# LED_Validation_Board_pg_1.net
KiCad netlist of a schematic drawn in Altium Designer
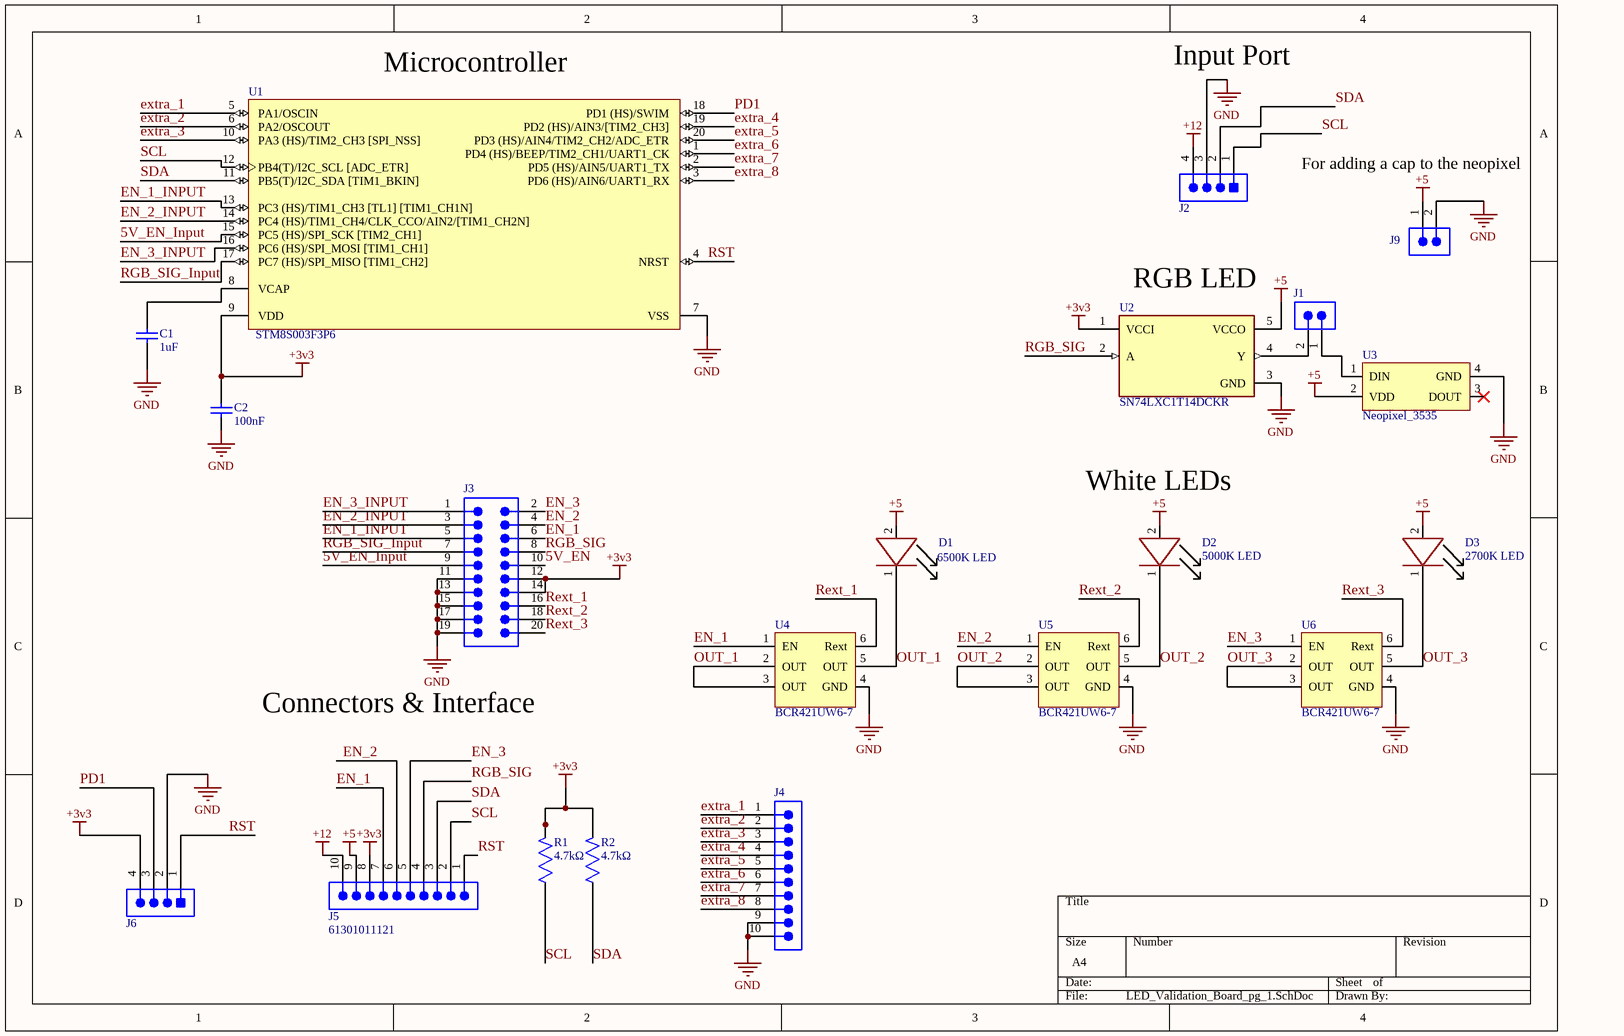
[diagram p0: LED_Validation_Board_pg_1.SchDoc]

(export (version "E")
  (design (tool "Eeschema 10.0.6"))
  (components
    (comp (ref "C1")
      (value "1uF")
      (footprint "0402 PACKAGE")
      (description "CAP CER 1UF 10V X5R 0402")
      (libsource (lib "LED_Validation_Sch_Lib") (part "Capacitor"))
    )
    (comp (ref "C2")
      (value "100nF")
      (footprint "0402 PACKAGE")
      (description "CAP CER 0.1UF 10V X5R 0402")
      (libsource (lib "LED_Validation_Sch_Lib") (part "Capacitor"))
    )
    (comp (ref "D1")
      (value "6500K LED")
      (footprint "2424 Package")
      (description "6500k LED")
      (libsource (lib "LED_Module_Schematic_Library") (part "6500K LED"))
    )
    (comp (ref "D2")
      (value "5000K LED")
      (footprint "2424 Package")
      (description "5000k LED")
      (libsource (lib "LED_Module_Schematic_Library") (part "5000K LED"))
    )
    (comp (ref "D3")
      (value "2700K LED")
      (footprint "2424 Package")
      (description "2700k LED")
      (libsource (lib "LED_Module_Schematic_Library") (part "2700K LED"))
    )
    (comp (ref "J1")
      (value "TSW-102-26-F-S")
      (footprint "SMTC-TSW-102-26-XX-S")
      (description "0.025\" SQ Post Header, Through-hole, Vertical, -55 to 125 degC, 2.54 mm Pitch, 2-Pin, Male, RoHS")
      (fields (field (name "MANUFACTURER") "Samtec"))
      (libsource (lib "Altium Content Vault") (part "SMTC-TSW-102-X-X-S-X"))
    )
    (comp (ref "J2")
      (value "640445-4")
      (footprint "TECO-640445-4_V")
      (fields (field (name "MANUFACTURER") "TE Connectivity"))
      (libsource (lib "Altium Content Vault") (part "CN-1P-M-R4"))
    )
    (comp (ref "J3")
      (value "61302021121")
      (footprint "61302021121")
      (libsource (lib "Altium Content Vault") (part "Header_Male_2R_20P"))
    )
    (comp (ref "J4")
      (value "61301011121")
      (footprint "61301011121")
      (libsource (lib "Altium Content Vault") (part "Header_Male_1R_10P"))
    )
    (comp (ref "J5")
      (value "61301011121")
      (footprint "61301011121")
      (libsource (lib "Altium Content Vault") (part "Header_Male_1R_10P"))
    )
    (comp (ref "J6")
      (value "640445-4")
      (footprint "TECO-640445-4_V")
      (fields (field (name "MANUFACTURER") "TE Connectivity"))
      (libsource (lib "Altium Content Vault") (part "CN-1P-M-R4"))
    )
    (comp (ref "J9")
      (value "TSW-102-26-F-S")
      (footprint "SMTC-TSW-102-26-XX-S")
      (description "0.025\" SQ Post Header, Through-hole, Vertical, -55 to 125 degC, 2.54 mm Pitch, 2-Pin, Male, RoHS")
      (fields (field (name "MANUFACTURER") "Samtec"))
      (libsource (lib "Altium Content Vault") (part "SMTC-TSW-102-X-X-S-X"))
    )
    (comp (ref "R1")
      (value "4.7kΩ")
      (footprint "0402 PACKAGE")
      (libsource (lib "LED_Validation_Sch_Lib") (part "Resistor"))
    )
    (comp (ref "R2")
      (value "4.7kΩ")
      (footprint "0402 PACKAGE")
      (libsource (lib "LED_Validation_Sch_Lib") (part "Resistor"))
    )
    (comp (ref "U1")
      (value "STM8S003F3P6")
      (footprint "STM-TSSOP20_V")
      (fields (field (name "MANUFACTURER") "STMicroelectronics"))
      (libsource (lib "Altium Content Vault") (part "STM-STM8S003F3P6-TSSOP20"))
    )
    (comp (ref "U2")
      (value "SN74LXC1T14DCKR")
      (footprint "FP-DCK0005A-MFG")
      (description "IC TRANSLATOR UNIDIR SC70-5")
      (libsource (lib "Altium Content Vault") (part "307c293e8a03021d4f984951ede828e"))
    )
    (comp (ref "U3")
      (value "Neopixel_3535")
      (footprint "Neopixel")
      (libsource (lib "LED_Validation_Sch_Lib") (part "Neopixel_3535"))
    )
    (comp (ref "U4")
      (value "BCR421UW6-7")
      (footprint "SOT95P280X140-6N")
      (description "LED Driver")
      (libsource (lib "LED_Validation_Sch_Lib") (part "BCR421UW6-7"))
    )
    (comp (ref "U5")
      (value "BCR421UW6-7")
      (footprint "SOT95P280X140-6N")
      (description "LED Driver")
      (libsource (lib "LED_Validation_Sch_Lib") (part "BCR421UW6-7"))
    )
    (comp (ref "U6")
      (value "BCR421UW6-7")
      (footprint "SOT95P280X140-6N")
      (description "LED Driver")
      (libsource (lib "LED_Validation_Sch_Lib") (part "BCR421UW6-7"))
    )
  )
  (nets
    (net (code "1") (name "+3v3") (class "Default")
      (node (ref "C2") (pin "2") (pinfunction "2_2") (pintype "passive"))
      (node (ref "J3") (pin "12") (pinfunction "12_12") (pintype "passive"))
      (node (ref "J3") (pin "14") (pinfunction "14_14") (pintype "passive"))
      (node (ref "J5") (pin "8") (pinfunction "8_8") (pintype "passive"))
      (node (ref "J6") (pin "4") (pinfunction "4_4") (pintype "passive"))
      (node (ref "R1") (pin "2") (pinfunction "2_2") (pintype "passive"))
      (node (ref "R2") (pin "2") (pinfunction "2_2") (pintype "passive"))
      (node (ref "U1") (pin "9") (pinfunction "VDD_9") (pintype "power_in"))
      (node (ref "U2") (pin "1") (pinfunction "VCCI_1") (pintype "power_in"))
    )
    (net (code "2") (name "+5") (class "Default")
      (node (ref "D1") (pin "2") (pinfunction "2_2") (pintype "passive"))
      (node (ref "D2") (pin "2") (pinfunction "2_2") (pintype "passive"))
      (node (ref "D3") (pin "2") (pinfunction "2_2") (pintype "passive"))
      (node (ref "J5") (pin "9") (pinfunction "9_9") (pintype "passive"))
      (node (ref "J9") (pin "1") (pinfunction "1_1") (pintype "passive"))
      (node (ref "U2") (pin "5") (pinfunction "VCCO_5") (pintype "power_in"))
      (node (ref "U3") (pin "2") (pinfunction "VDD_2") (pintype "passive"))
    )
    (net (code "3") (name "+12") (class "Default")
      (node (ref "J2") (pin "4") (pinfunction "4_4") (pintype "passive"))
      (node (ref "J5") (pin "10") (pinfunction "10_10") (pintype "passive"))
    )
    (net (code "4") (name "/5V_EN") (class "Default")
      (node (ref "J3") (pin "10") (pinfunction "10_10") (pintype "passive"))
    )
    (net (code "5") (name "/5V_EN_Input") (class "Default")
      (node (ref "J3") (pin "9") (pinfunction "9_9") (pintype "passive"))
      (node (ref "U1") (pin "15") (pinfunction "PC5_(HS)/SPI_SCK_[TIM2_CH1]_15") (pintype "bidirectional"))
    )
    (net (code "6") (name "/EN_1") (class "Default")
      (node (ref "J3") (pin "6") (pinfunction "6_6") (pintype "passive"))
      (node (ref "J5") (pin "7") (pinfunction "7_7") (pintype "passive"))
      (node (ref "U4") (pin "1") (pinfunction "EN_1") (pintype "passive"))
    )
    (net (code "7") (name "/EN_1_INPUT") (class "Default")
      (node (ref "J3") (pin "5") (pinfunction "5_5") (pintype "passive"))
      (node (ref "U1") (pin "13") (pinfunction "PC3_(HS)/TIM1_CH3_[TL1]_[TIM1_CH1N]_13") (pintype "bidirectional"))
    )
    (net (code "8") (name "/EN_2") (class "Default")
      (node (ref "J3") (pin "4") (pinfunction "4_4") (pintype "passive"))
      (node (ref "J5") (pin "6") (pinfunction "6_6") (pintype "passive"))
      (node (ref "U5") (pin "1") (pinfunction "EN_1") (pintype "passive"))
    )
    (net (code "9") (name "/EN_2_INPUT") (class "Default")
      (node (ref "J3") (pin "3") (pinfunction "3_3") (pintype "passive"))
      (node (ref "U1") (pin "14") (pinfunction "PC4_(HS)/TIM1_CH4/CLK_CCO/AIN2/[TIM1_CH2N]_14") (pintype "bidirectional"))
    )
    (net (code "10") (name "/EN_3") (class "Default")
      (node (ref "J3") (pin "2") (pinfunction "2_2") (pintype "passive"))
      (node (ref "J5") (pin "5") (pinfunction "5_5") (pintype "passive"))
      (node (ref "U6") (pin "1") (pinfunction "EN_1") (pintype "passive"))
    )
    (net (code "11") (name "/EN_3_INPUT") (class "Default")
      (node (ref "J3") (pin "1") (pinfunction "1_1") (pintype "passive"))
      (node (ref "U1") (pin "16") (pinfunction "PC6_(HS)/SPI_MOSI_[TIM1_CH1]_16") (pintype "bidirectional"))
    )
    (net (code "12") (name "/OUT_1") (class "Default")
      (node (ref "D1") (pin "1") (pinfunction "1_1") (pintype "passive"))
      (node (ref "U4") (pin "2") (pinfunction "OUT_2") (pintype "passive"))
      (node (ref "U4") (pin "3") (pinfunction "OUT_3") (pintype "passive"))
      (node (ref "U4") (pin "5") (pinfunction "OUT_5") (pintype "passive"))
    )
    (net (code "13") (name "/OUT_2") (class "Default")
      (node (ref "D2") (pin "1") (pinfunction "1_1") (pintype "passive"))
      (node (ref "U5") (pin "2") (pinfunction "OUT_2") (pintype "passive"))
      (node (ref "U5") (pin "3") (pinfunction "OUT_3") (pintype "passive"))
      (node (ref "U5") (pin "5") (pinfunction "OUT_5") (pintype "passive"))
    )
    (net (code "14") (name "/OUT_3") (class "Default")
      (node (ref "D3") (pin "1") (pinfunction "1_1") (pintype "passive"))
      (node (ref "U6") (pin "2") (pinfunction "OUT_2") (pintype "passive"))
      (node (ref "U6") (pin "3") (pinfunction "OUT_3") (pintype "passive"))
      (node (ref "U6") (pin "5") (pinfunction "OUT_5") (pintype "passive"))
    )
    (net (code "15") (name "/PD1") (class "Default")
      (node (ref "J6") (pin "3") (pinfunction "3_3") (pintype "passive"))
      (node (ref "U1") (pin "18") (pinfunction "PD1_(HS)/SWIM_18") (pintype "bidirectional"))
    )
    (net (code "16") (name "/RGB_SIG") (class "Default")
      (node (ref "J3") (pin "8") (pinfunction "8_8") (pintype "passive"))
      (node (ref "J5") (pin "4") (pinfunction "4_4") (pintype "passive"))
      (node (ref "U2") (pin "2") (pinfunction "A_2") (pintype "input"))
    )
    (net (code "17") (name "/RGB_SIG_Input") (class "Default")
      (node (ref "J3") (pin "7") (pinfunction "7_7") (pintype "passive"))
      (node (ref "U1") (pin "17") (pinfunction "PC7_(HS)/SPI_MISO_[TIM1_CH2]_17") (pintype "bidirectional"))
    )
    (net (code "18") (name "/RST") (class "Default")
      (node (ref "J5") (pin "1") (pinfunction "1_1") (pintype "passive"))
      (node (ref "J6") (pin "1") (pinfunction "1_1") (pintype "passive"))
      (node (ref "U1") (pin "4") (pinfunction "NRST_4") (pintype "bidirectional"))
    )
    (net (code "19") (name "/Rext_1") (class "Default")
      (node (ref "J3") (pin "16") (pinfunction "16_16") (pintype "passive"))
      (node (ref "U4") (pin "6") (pinfunction "Rext_6") (pintype "passive"))
    )
    (net (code "20") (name "/Rext_2") (class "Default")
      (node (ref "J3") (pin "18") (pinfunction "18_18") (pintype "passive"))
      (node (ref "U5") (pin "6") (pinfunction "Rext_6") (pintype "passive"))
    )
    (net (code "21") (name "/Rext_3") (class "Default")
      (node (ref "J3") (pin "20") (pinfunction "20_20") (pintype "passive"))
      (node (ref "U6") (pin "6") (pinfunction "Rext_6") (pintype "passive"))
    )
    (net (code "22") (name "/SCL") (class "Default")
      (node (ref "J2") (pin "1") (pinfunction "1_1") (pintype "passive"))
      (node (ref "J5") (pin "2") (pinfunction "2_2") (pintype "passive"))
      (node (ref "R1") (pin "1") (pinfunction "1_1") (pintype "passive"))
      (node (ref "U1") (pin "12") (pinfunction "PB4(T)/I2C_SCL_[ADC_ETR]_12") (pintype "bidirectional"))
    )
    (net (code "23") (name "/SDA") (class "Default")
      (node (ref "J2") (pin "2") (pinfunction "2_2") (pintype "passive"))
      (node (ref "J5") (pin "3") (pinfunction "3_3") (pintype "passive"))
      (node (ref "R2") (pin "1") (pinfunction "1_1") (pintype "passive"))
      (node (ref "U1") (pin "11") (pinfunction "PB5(T)/I2C_SDA_[TIM1_BKIN]_11") (pintype "bidirectional"))
    )
    (net (code "24") (name "/extra_1") (class "Default")
      (node (ref "J4") (pin "1") (pinfunction "1_1") (pintype "passive"))
      (node (ref "U1") (pin "5") (pinfunction "PA1/OSCIN_5") (pintype "bidirectional"))
    )
    (net (code "25") (name "/extra_2") (class "Default")
      (node (ref "J4") (pin "2") (pinfunction "2_2") (pintype "passive"))
      (node (ref "U1") (pin "6") (pinfunction "PA2/OSCOUT_6") (pintype "bidirectional"))
    )
    (net (code "26") (name "/extra_3") (class "Default")
      (node (ref "J4") (pin "3") (pinfunction "3_3") (pintype "passive"))
      (node (ref "U1") (pin "10") (pinfunction "PA3_(HS)/TIM2_CH3_[SPI_NSS]_10") (pintype "bidirectional"))
    )
    (net (code "27") (name "/extra_4") (class "Default")
      (node (ref "J4") (pin "4") (pinfunction "4_4") (pintype "passive"))
      (node (ref "U1") (pin "19") (pinfunction "PD2_(HS)/AIN3/[TIM2_CH3]_19") (pintype "bidirectional"))
    )
    (net (code "28") (name "/extra_5") (class "Default")
      (node (ref "J4") (pin "5") (pinfunction "5_5") (pintype "passive"))
      (node (ref "U1") (pin "20") (pinfunction "PD3_(HS)/AIN4/TIM2_CH2/ADC_ETR_20") (pintype "bidirectional"))
    )
    (net (code "29") (name "/extra_6") (class "Default")
      (node (ref "J4") (pin "6") (pinfunction "6_6") (pintype "passive"))
      (node (ref "U1") (pin "1") (pinfunction "PD4_(HS)/BEEP/TIM2_CH1/UART1_CK_1") (pintype "bidirectional"))
    )
    (net (code "30") (name "/extra_7") (class "Default")
      (node (ref "J4") (pin "7") (pinfunction "7_7") (pintype "passive"))
      (node (ref "U1") (pin "2") (pinfunction "PD5_(HS)/AIN5/UART1_TX_2") (pintype "bidirectional"))
    )
    (net (code "31") (name "/extra_8") (class "Default")
      (node (ref "J4") (pin "8") (pinfunction "8_8") (pintype "passive"))
      (node (ref "U1") (pin "3") (pinfunction "PD6_(HS)/AIN6/UART1_RX_3") (pintype "bidirectional"))
    )
    (net (code "32") (name "GND") (class "Default")
      (node (ref "C1") (pin "1") (pinfunction "1_1") (pintype "passive"))
      (node (ref "C2") (pin "1") (pinfunction "1_1") (pintype "passive"))
      (node (ref "J2") (pin "3") (pinfunction "3_3") (pintype "passive"))
      (node (ref "J3") (pin "11") (pinfunction "11_11") (pintype "passive"))
      (node (ref "J3") (pin "13") (pinfunction "13_13") (pintype "passive"))
      (node (ref "J3") (pin "15") (pinfunction "15_15") (pintype "passive"))
      (node (ref "J3") (pin "17") (pinfunction "17_17") (pintype "passive"))
      (node (ref "J3") (pin "19") (pinfunction "19_19") (pintype "passive"))
      (node (ref "J4") (pin "10") (pinfunction "10_10") (pintype "passive"))
      (node (ref "J4") (pin "9") (pinfunction "9_9") (pintype "passive"))
      (node (ref "J6") (pin "2") (pinfunction "2_2") (pintype "passive"))
      (node (ref "J9") (pin "2") (pinfunction "2_2") (pintype "passive"))
      (node (ref "U1") (pin "7") (pinfunction "VSS_7") (pintype "power_in"))
      (node (ref "U2") (pin "3") (pinfunction "GND_3") (pintype "power_in"))
      (node (ref "U3") (pin "4") (pinfunction "GND_4") (pintype "passive"))
      (node (ref "U4") (pin "4") (pinfunction "GND_4") (pintype "passive"))
      (node (ref "U5") (pin "4") (pinfunction "GND_4") (pintype "passive"))
      (node (ref "U6") (pin "4") (pinfunction "GND_4") (pintype "passive"))
    )
    (net (code "33") (name "Net-(U1-VCAP)") (class "Default")
      (node (ref "C1") (pin "2") (pinfunction "2_2") (pintype "passive"))
      (node (ref "U1") (pin "8") (pinfunction "VCAP_8") (pintype "power_in"))
    )
    (net (code "34") (name "Net-(U2-Y)") (class "Default")
      (node (ref "J1") (pin "2") (pinfunction "2_2") (pintype "passive"))
      (node (ref "U2") (pin "4") (pinfunction "Y_4") (pintype "output"))
    )
    (net (code "35") (name "Net-(U3-DIN)") (class "Default")
      (node (ref "J1") (pin "1") (pinfunction "1_1") (pintype "passive"))
      (node (ref "U3") (pin "1") (pinfunction "DIN_1") (pintype "passive"))
    )
    (net (code "36") (name "unconnected-(U3-DOUT-Pad3)") (class "Default")
      (node (ref "U3") (pin "3") (pinfunction "DOUT_3") (pintype "passive+no_connect"))
    )
  )
)
